# SCH_SrProj_v1_4.net
KiCad netlist of a schematic drawn in EasyEDA
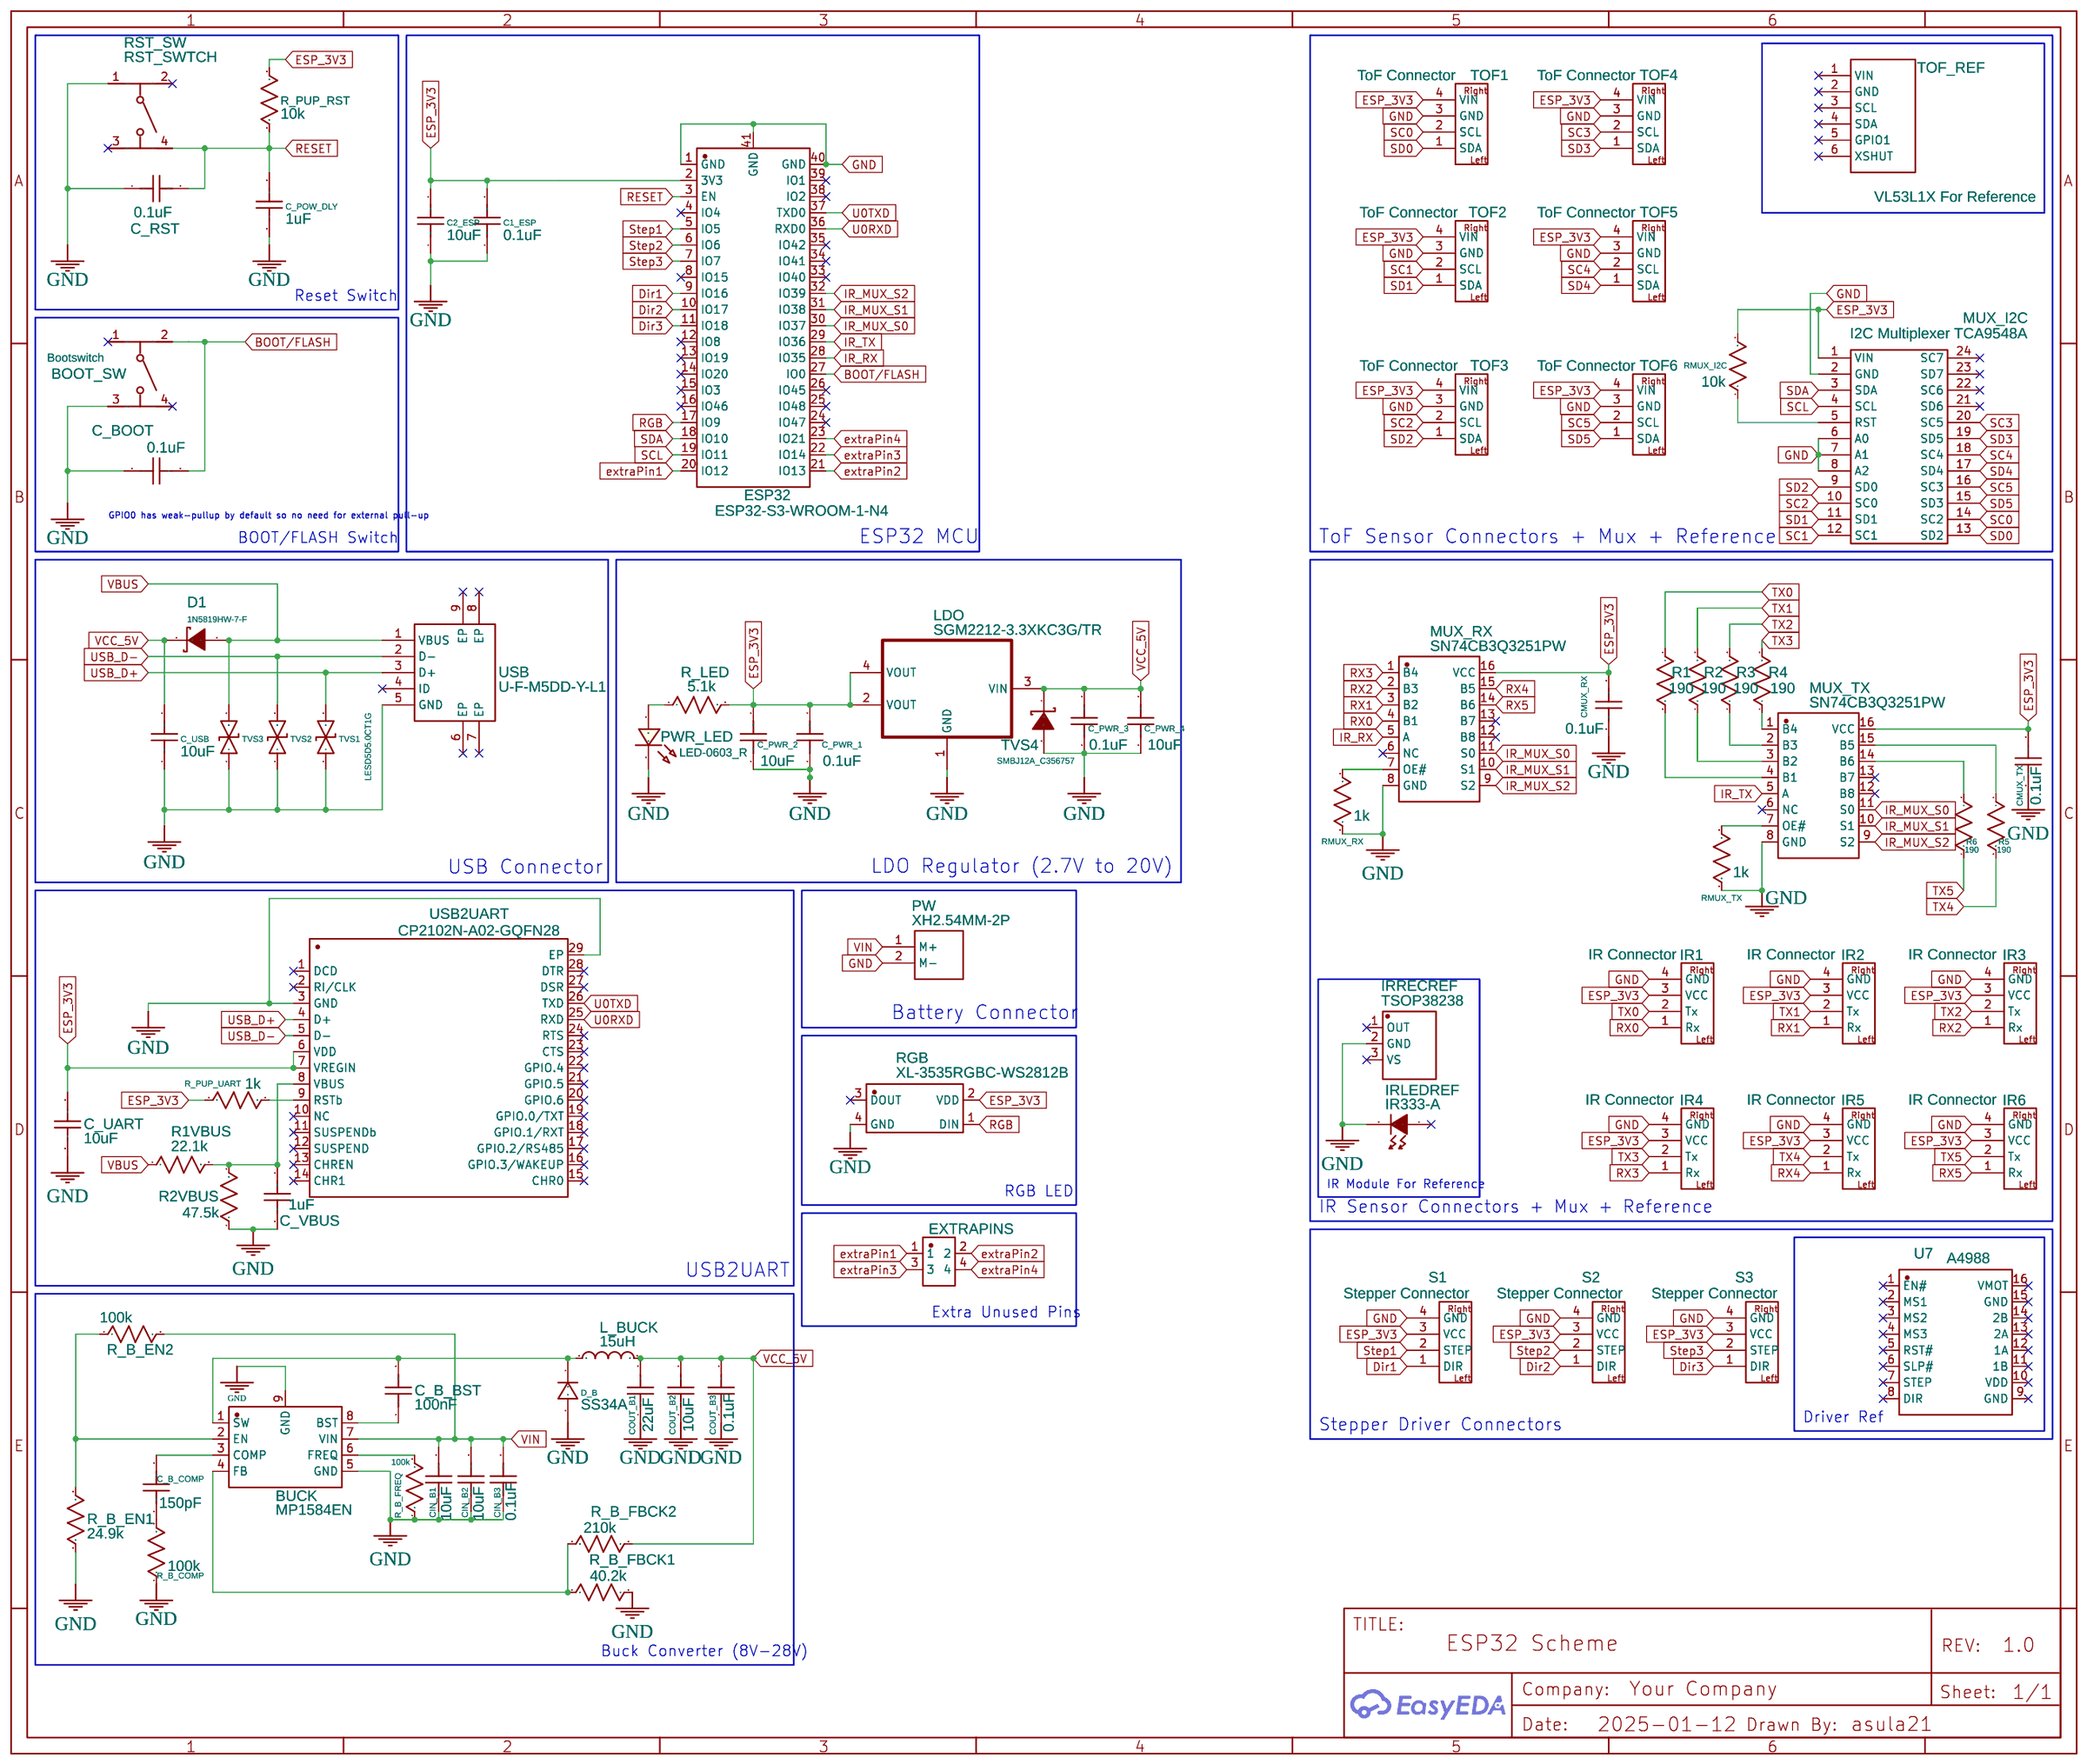
[diagram p0: schematic sheet]

(export (version "E")
  (design (tool "Eeschema 10.0.6"))
  (components
    (comp (ref "BOOT_SW")
      (value "Bootswitch")
      (fields
        (field (name "Manufacturer Part") "Switch,6*6*6Plastic head,260G, 0.25mm,Straight line")
        (field (name "Manufacturer") "BBJ")
      )
      (libsource (lib "") (part "Button-6x6x6mm_1"))
    )
    (comp (ref "BUCK") (value "MP1584EN") (libsource (lib "") (part "MP1584EN")))
    (comp (ref "C1_ESP") (value "0.1uF") (libsource (lib "") (part "C_0603_US_13")))
    (comp (ref "C2_ESP") (value "10uF") (libsource (lib "") (part "C_0603_US_12")))
    (comp (ref "CIN_B1") (value "10uF") (libsource (lib "") (part "C_0603_US_3")))
    (comp (ref "CIN_B2") (value "10uF") (libsource (lib "") (part "C_0603_US_3")))
    (comp (ref "CIN_B3") (value "0.1uF") (libsource (lib "") (part "C_0603_US_3")))
    (comp (ref "CMUX_RX") (value "0.1uF") (libsource (lib "") (part "C_0603_US_10")))
    (comp (ref "CMUX_TX") (value "0.1uF") (libsource (lib "") (part "C_0603_US_5")))
    (comp (ref "COUT_B1") (value "22uF") (libsource (lib "") (part "C_0603_US")))
    (comp (ref "COUT_B2") (value "10uF") (libsource (lib "") (part "C_0603_US")))
    (comp (ref "COUT_B3") (value "0.1uF") (libsource (lib "") (part "C_0603_US")))
    (comp (ref "C_BOOT") (value "0.1uF") (libsource (lib "") (part "C_0603_US_1")))
    (comp (ref "C_B_BST") (value "100nF") (libsource (lib "") (part "C_0603_US_7")))
    (comp (ref "C_B_COMP") (value "150pF") (libsource (lib "") (part "C_0603_US_8")))
    (comp (ref "C_POW_DLY") (value "1uF") (libsource (lib "") (part "C_0603_US_11")))
    (comp (ref "C_PWR_1") (value "0.1uF") (libsource (lib "") (part "C_0603_US_6")))
    (comp (ref "C_PWR_2") (value "10uF") (libsource (lib "") (part "C_0603_US_6")))
    (comp (ref "C_PWR_3") (value "0.1uF") (libsource (lib "") (part "C_0603_US_6")))
    (comp (ref "C_PWR_4") (value "10uF") (libsource (lib "") (part "C_0603_US_6")))
    (comp (ref "C_RST") (value "0.1uF") (libsource (lib "") (part "C_0603_US_9")))
    (comp (ref "C_UART") (value "10uF") (libsource (lib "") (part "C_0603_US_4")))
    (comp (ref "C_USB") (value "10uF") (libsource (lib "") (part "C_0603_US_14")))
    (comp (ref "C_VBUS") (value "1uF") (libsource (lib "") (part "C_0603_US_2")))
    (comp (ref "D1")
      (value "1N5819HW-7-F")
      (fields (field (name "Manufacturer") "DIODES(美台)"))
      (libsource (lib "") (part "1N5819HW-7-F"))
    )
    (comp (ref "D_B")
      (value "SS34A")
      (fields (field (name "Manufacturer") "YANGJIE(扬杰)"))
      (libsource (lib "") (part "SS34A"))
    )
    (comp (ref "ESP32")
      (value "ESP32-S3-WROOM-1-N4")
      (fields (field (name "Manufacturer") "ESPRESSIF(乐鑫)"))
      (libsource (lib "") (part "ESP32-S3-WROOM-1-N4"))
    )
    (comp (ref "EXTRAPINS")
      (value "排母/2.54MM2X2直排母袋装环保")
      (fields
        (field (name "Manufacturer Part") "排母/2.54mm2x2直排母袋装环保")
        (field (name "Manufacturer") "BOOMELE(博穆精密)")
      )
      (libsource (lib "") (part "排母/2.54MM2X2直排母袋装环保"))
    )
    (comp (ref "IR1") (value "IR Connector") (libsource (lib "") (part "MY XH2.54MM.4P_1")))
    (comp (ref "IR2") (value "IR Connector") (libsource (lib "") (part "MY XH2.54MM.4P_1")))
    (comp (ref "IR3") (value "IR Connector") (libsource (lib "") (part "MY XH2.54MM.4P_1")))
    (comp (ref "IR4") (value "IR Connector") (libsource (lib "") (part "MY XH2.54MM.4P_1")))
    (comp (ref "IR5") (value "IR Connector") (libsource (lib "") (part "MY XH2.54MM.4P_1")))
    (comp (ref "IR6") (value "IR Connector") (libsource (lib "") (part "MY XH2.54MM.4P_1")))
    (comp (ref "IRLEDREF")
      (value "IR333-A")
      (fields (field (name "Manufacturer") "EVERLIGHT(亿光)"))
      (libsource (lib "") (part "IR333-A"))
    )
    (comp (ref "IRRECREF")
      (value "TSOP38238")
      (fields (field (name "Manufacturer") "VISHAY(威世)"))
      (libsource (lib "") (part "TSOP38238"))
    )
    (comp (ref "LDO") (value "SGM2212-3.3XKC3G/TR") (libsource (lib "") (part "SGM2212-3.3XKC3G/TR")))
    (comp (ref "L_BUCK")
      (value "15uH")
      (fields (field (name "Manufacturer Part") "CYH127-4.7UH") (field (name "Manufacturer") "SHOU HAN(首韩)"))
      (libsource (lib "") (part "CYH127-4.7UH"))
    )
    (comp (ref "MUX_I2C")
      (value "I2C Multiplexer TCA9548A")
      (fields (field (name "Manufacturer Part") "IDSN-TCA9548A") (field (name "Manufacturer") "IDSN"))
      (libsource (lib "") (part "TCA9548A I2C MULTIPLEXER 8 CHANEL"))
    )
    (comp (ref "MUX_RX")
      (value "SN74CB3Q3251PW")
      (fields (field (name "Manufacturer") "TI(德州仪器)"))
      (libsource (lib "") (part "SN74CB3Q3251PW"))
    )
    (comp (ref "MUX_TX")
      (value "SN74CB3Q3251PW")
      (fields (field (name "Manufacturer") "TI(德州仪器)"))
      (libsource (lib "") (part "SN74CB3Q3251PW_1"))
    )
    (comp (ref "PW")
      (value "XH2.54MM-2P")
      (fields (field (name "Manufacturer Part") "Header P2 PH2.0 TUANLE"))
      (libsource (lib "") (part "PH2.0-2P"))
    )
    (comp (ref "PWR_LED")
      (value "LED-0603_R")
      (fields
        (field (name "Manufacturer Part") "19-217/R6C-AL1M2VY/3T")
        (field (name "Manufacturer") "EVERLIGHT(台湾亿光)")
      )
      (libsource (lib "") (part "LED-0603_R"))
    )
    (comp (ref "R1") (value "190") (libsource (lib "") (part "R_0805_US_1")))
    (comp (ref "R1VBUS") (value "22.1k") (libsource (lib "") (part "R_0603_US_1")))
    (comp (ref "R2") (value "190") (libsource (lib "") (part "R_0805_US")))
    (comp (ref "R2VBUS") (value "47.5k") (libsource (lib "") (part "R_0603_US_3")))
    (comp (ref "R3") (value "190") (libsource (lib "") (part "R_0805_US")))
    (comp (ref "R4") (value "190") (libsource (lib "") (part "R_0805_US")))
    (comp (ref "R5") (value "190") (libsource (lib "") (part "R_0805_US_1")))
    (comp (ref "R6") (value "190") (libsource (lib "") (part "R_0805_US")))
    (comp (ref "RGB")
      (value "XL-3535RGBC-WS2812B")
      (fields (field (name "Manufacturer") "XINGLIGHT(成兴光)"))
      (libsource (lib "") (part "XL-3535RGBC-WS2812B"))
    )
    (comp (ref "RMUX_I2C") (value "10k") (libsource (lib "") (part "R_0603_US_2")))
    (comp (ref "RMUX_RX") (value "1k") (libsource (lib "") (part "R_0603_US_12")))
    (comp (ref "RMUX_TX") (value "1k") (libsource (lib "") (part "R_0603_US_11")))
    (comp (ref "RST_SW")
      (value "RST_SWTCH")
      (fields
        (field (name "Manufacturer Part") "Switch,6*6*6Plastic head,260G, 0.25mm,Straight line")
        (field (name "Manufacturer") "BBJ")
      )
      (libsource (lib "") (part "Button-6x6x6mm"))
    )
    (comp (ref "R_B_COMP") (value "100k") (libsource (lib "") (part "R_0603_US_5")))
    (comp (ref "R_B_EN1") (value "24.9k") (libsource (lib "") (part "R_0603_US_6")))
    (comp (ref "R_B_EN2") (value "100k") (libsource (lib "") (part "R_0603_US")))
    (comp (ref "R_B_FBCK1") (value "40.2k") (libsource (lib "") (part "R_0603_US_13")))
    (comp (ref "R_B_FBCK2") (value "210k") (libsource (lib "") (part "R_0603_US_4")))
    (comp (ref "R_B_FREQ") (value "100k") (libsource (lib "") (part "R_0603_US_9")))
    (comp (ref "R_LED") (value "5.1k") (libsource (lib "") (part "R_0603_US_7")))
    (comp (ref "R_PUP_RST") (value "10k") (libsource (lib "") (part "R_0603_US_8")))
    (comp (ref "R_PUP_UART") (value "1k") (libsource (lib "") (part "R_0603_US_10")))
    (comp (ref "S1") (value "Stepper Connector") (libsource (lib "") (part "MY XH2.54MM.4P_2")))
    (comp (ref "S2") (value "Stepper Connector") (libsource (lib "") (part "MY XH2.54MM.4P_2")))
    (comp (ref "S3") (value "Stepper Connector") (libsource (lib "") (part "MY XH2.54MM.4P_2")))
    (comp (ref "TOF1") (value "ToF Connector") (libsource (lib "") (part "MY XH2.54MM.4P")))
    (comp (ref "TOF2") (value "ToF Connector") (libsource (lib "") (part "MY XH2.54MM.4P")))
    (comp (ref "TOF3") (value "ToF Connector") (libsource (lib "") (part "MY XH2.54MM.4P")))
    (comp (ref "TOF4") (value "ToF Connector") (libsource (lib "") (part "MY XH2.54MM.4P")))
    (comp (ref "TOF5") (value "ToF Connector") (libsource (lib "") (part "MY XH2.54MM.4P")))
    (comp (ref "TOF6") (value "ToF Connector") (libsource (lib "") (part "MY XH2.54MM.4P")))
    (comp (ref "TOF_REF")
      (value "VL53L1X For Reference")
      (fields (field (name "Manufacturer Part") "VL53L0X Time-of-Flight Distance Sensor VL53L0X"))
      (libsource (lib "") (part "VL53L1X_BREAKOUT"))
    )
    (comp (ref "TVS1")
      (value "LESD5D5.0CT1G")
      (fields (field (name "Manufacturer") "LRC(乐山无线电)"))
      (libsource (lib "") (part "LESD5D5.0CT1G"))
    )
    (comp (ref "TVS2")
      (value "LESD5D5.0CT1G")
      (fields (field (name "Manufacturer") "LRC(乐山无线电)"))
      (libsource (lib "") (part "LESD5D5.0CT1G"))
    )
    (comp (ref "TVS3")
      (value "LESD5D5.0CT1G")
      (fields (field (name "Manufacturer") "LRC(乐山无线电)"))
      (libsource (lib "") (part "LESD5D5.0CT1G"))
    )
    (comp (ref "TVS4")
      (value "SMBJ12A_C356757")
      (fields (field (name "Manufacturer Part") "SMBJ12A") (field (name "Manufacturer") "JJW(捷捷微)"))
      (libsource (lib "") (part "SMBJ12A_C356757"))
    )
    (comp (ref "U7") (value "A4988") (libsource (lib "") (part "A4988")))
    (comp (ref "USB")
      (value "U-F-M5DD-Y-L1")
      (fields (field (name "Manufacturer") "韩国韩荣"))
      (libsource (lib "") (part "U-F-M5DD-Y-L1"))
    )
    (comp (ref "USB2UART")
      (value "CP2102N-A02-GQFN28")
      (fields (field (name "Manufacturer") "SKYWORKS/SILICON LABS(芯科)"))
      (libsource (lib "") (part "CP2102N-A02-GQFN28"))
    )
  )
  (nets
    (net (code "1") (name "BOOT{slash}FLASH") (class "Default")
      (node (ref "BOOT_SW") (pin "2") (pinfunction "2_2") (pintype "unspecified"))
      (node (ref "C_BOOT") (pin "2") (pinfunction "2_2") (pintype "unspecified"))
      (node (ref "ESP32") (pin "27") (pinfunction "IO0_27") (pintype "unspecified"))
    )
    (net (code "2") (name "Dir1") (class "Default")
      (node (ref "ESP32") (pin "9") (pinfunction "IO16_9") (pintype "unspecified"))
      (node (ref "S1") (pin "1") (pinfunction "DIR_1") (pintype "unspecified"))
    )
    (net (code "3") (name "Dir2") (class "Default")
      (node (ref "ESP32") (pin "10") (pinfunction "IO17_10") (pintype "unspecified"))
      (node (ref "S2") (pin "1") (pinfunction "DIR_1") (pintype "unspecified"))
    )
    (net (code "4") (name "Dir3") (class "Default")
      (node (ref "ESP32") (pin "11") (pinfunction "IO18_11") (pintype "unspecified"))
      (node (ref "S3") (pin "1") (pinfunction "DIR_1") (pintype "unspecified"))
    )
    (net (code "5") (name "ESP_3V3") (class "Default")
      (node (ref "C1_ESP") (pin "2") (pinfunction "2_2") (pintype "unspecified"))
      (node (ref "C2_ESP") (pin "2") (pinfunction "2_2") (pintype "unspecified"))
      (node (ref "CMUX_RX") (pin "2") (pinfunction "2_2") (pintype "unspecified"))
      (node (ref "CMUX_TX") (pin "2") (pinfunction "2_2") (pintype "unspecified"))
      (node (ref "C_PWR_1") (pin "2") (pinfunction "2_2") (pintype "unspecified"))
      (node (ref "C_PWR_2") (pin "2") (pinfunction "2_2") (pintype "unspecified"))
      (node (ref "C_UART") (pin "2") (pinfunction "2_2") (pintype "unspecified"))
      (node (ref "ESP32") (pin "2") (pinfunction "3V3_2") (pintype "unspecified"))
      (node (ref "IR1") (pin "3") (pinfunction "VCC_3") (pintype "unspecified"))
      (node (ref "IR2") (pin "3") (pinfunction "VCC_3") (pintype "unspecified"))
      (node (ref "IR3") (pin "3") (pinfunction "VCC_3") (pintype "unspecified"))
      (node (ref "IR4") (pin "3") (pinfunction "VCC_3") (pintype "unspecified"))
      (node (ref "IR5") (pin "3") (pinfunction "VCC_3") (pintype "unspecified"))
      (node (ref "IR6") (pin "3") (pinfunction "VCC_3") (pintype "unspecified"))
      (node (ref "LDO") (pin "2") (pinfunction "VOUT_2") (pintype "unspecified"))
      (node (ref "LDO") (pin "4") (pinfunction "VOUT_4") (pintype "unspecified"))
      (node (ref "MUX_I2C") (pin "1") (pinfunction "VIN_1") (pintype "unspecified"))
      (node (ref "MUX_RX") (pin "16") (pinfunction "VCC_16") (pintype "unspecified"))
      (node (ref "MUX_TX") (pin "16") (pinfunction "VCC_16") (pintype "unspecified"))
      (node (ref "RGB") (pin "2") (pinfunction "VDD_2") (pintype "unspecified"))
      (node (ref "RMUX_I2C") (pin "2") (pinfunction "2_2") (pintype "unspecified"))
      (node (ref "R_LED") (pin "2") (pinfunction "2_2") (pintype "unspecified"))
      (node (ref "R_PUP_RST") (pin "2") (pinfunction "2_2") (pintype "unspecified"))
      (node (ref "R_PUP_UART") (pin "2") (pinfunction "2_2") (pintype "unspecified"))
      (node (ref "S1") (pin "3") (pinfunction "VCC_3") (pintype "unspecified"))
      (node (ref "S2") (pin "3") (pinfunction "VCC_3") (pintype "unspecified"))
      (node (ref "S3") (pin "3") (pinfunction "VCC_3") (pintype "unspecified"))
      (node (ref "TOF1") (pin "4") (pinfunction "VIN_4") (pintype "unspecified"))
      (node (ref "TOF2") (pin "4") (pinfunction "VIN_4") (pintype "unspecified"))
      (node (ref "TOF3") (pin "4") (pinfunction "VIN_4") (pintype "unspecified"))
      (node (ref "TOF4") (pin "4") (pinfunction "VIN_4") (pintype "unspecified"))
      (node (ref "TOF5") (pin "4") (pinfunction "VIN_4") (pintype "unspecified"))
      (node (ref "TOF6") (pin "4") (pinfunction "VIN_4") (pintype "unspecified"))
      (node (ref "USB2UART") (pin "6") (pinfunction "VDD_6") (pintype "unspecified"))
      (node (ref "USB2UART") (pin "7") (pinfunction "VREGIN_7") (pintype "unspecified"))
    )
    (net (code "6") (name "GND") (class "Default")
      (node (ref "BOOT_SW") (pin "3") (pinfunction "3_3") (pintype "unspecified"))
      (node (ref "BUCK") (pin "5") (pinfunction "GND_5") (pintype "unspecified"))
      (node (ref "BUCK") (pin "9") (pinfunction "GND_9") (pintype "unspecified"))
      (node (ref "C1_ESP") (pin "1") (pinfunction "1_1") (pintype "unspecified"))
      (node (ref "C2_ESP") (pin "1") (pinfunction "1_1") (pintype "unspecified"))
      (node (ref "CIN_B1") (pin "1") (pinfunction "1_1") (pintype "unspecified"))
      (node (ref "CIN_B2") (pin "1") (pinfunction "1_1") (pintype "unspecified"))
      (node (ref "CIN_B3") (pin "1") (pinfunction "1_1") (pintype "unspecified"))
      (node (ref "CMUX_RX") (pin "1") (pinfunction "1_1") (pintype "unspecified"))
      (node (ref "CMUX_TX") (pin "1") (pinfunction "1_1") (pintype "unspecified"))
      (node (ref "COUT_B1") (pin "1") (pinfunction "1_1") (pintype "unspecified"))
      (node (ref "COUT_B2") (pin "1") (pinfunction "1_1") (pintype "unspecified"))
      (node (ref "COUT_B3") (pin "1") (pinfunction "1_1") (pintype "unspecified"))
      (node (ref "C_BOOT") (pin "1") (pinfunction "1_1") (pintype "unspecified"))
      (node (ref "C_POW_DLY") (pin "1") (pinfunction "1_1") (pintype "unspecified"))
      (node (ref "C_PWR_1") (pin "1") (pinfunction "1_1") (pintype "unspecified"))
      (node (ref "C_PWR_2") (pin "1") (pinfunction "1_1") (pintype "unspecified"))
      (node (ref "C_PWR_3") (pin "1") (pinfunction "1_1") (pintype "unspecified"))
      (node (ref "C_PWR_4") (pin "1") (pinfunction "1_1") (pintype "unspecified"))
      (node (ref "C_RST") (pin "1") (pinfunction "1_1") (pintype "unspecified"))
      (node (ref "C_UART") (pin "1") (pinfunction "1_1") (pintype "unspecified"))
      (node (ref "C_USB") (pin "1") (pinfunction "1_1") (pintype "unspecified"))
      (node (ref "C_VBUS") (pin "2") (pinfunction "2_2") (pintype "unspecified"))
      (node (ref "D_B") (pin "2") (pinfunction "A_2") (pintype "unspecified"))
      (node (ref "ESP32") (pin "1") (pinfunction "GND_1") (pintype "unspecified"))
      (node (ref "ESP32") (pin "40") (pinfunction "GND_40") (pintype "unspecified"))
      (node (ref "ESP32") (pin "41") (pinfunction "GND_41") (pintype "unspecified"))
      (node (ref "IR1") (pin "4") (pinfunction "GND_4") (pintype "unspecified"))
      (node (ref "IR2") (pin "4") (pinfunction "GND_4") (pintype "unspecified"))
      (node (ref "IR3") (pin "4") (pinfunction "GND_4") (pintype "unspecified"))
      (node (ref "IR4") (pin "4") (pinfunction "GND_4") (pintype "unspecified"))
      (node (ref "IR5") (pin "4") (pinfunction "GND_4") (pintype "unspecified"))
      (node (ref "IR6") (pin "4") (pinfunction "GND_4") (pintype "unspecified"))
      (node (ref "IRLEDREF") (pin "2") (pinfunction "C_2") (pintype "input"))
      (node (ref "IRRECREF") (pin "2") (pinfunction "GND_2") (pintype "unspecified"))
      (node (ref "LDO") (pin "1") (pinfunction "GND_1") (pintype "unspecified"))
      (node (ref "MUX_I2C") (pin "2") (pinfunction "GND_2") (pintype "unspecified"))
      (node (ref "MUX_I2C") (pin "6") (pinfunction "A0_6") (pintype "unspecified"))
      (node (ref "MUX_I2C") (pin "7") (pinfunction "A1_7") (pintype "unspecified"))
      (node (ref "MUX_I2C") (pin "8") (pinfunction "A2_8") (pintype "unspecified"))
      (node (ref "MUX_RX") (pin "8") (pinfunction "GND_8") (pintype "unspecified"))
      (node (ref "MUX_TX") (pin "8") (pinfunction "GND_8") (pintype "unspecified"))
      (node (ref "PW") (pin "2") (pinfunction "M-_2") (pintype "unspecified"))
      (node (ref "PWR_LED") (pin "2") (pinfunction "2_2") (pintype "unspecified"))
      (node (ref "R2VBUS") (pin "1") (pinfunction "1_1") (pintype "unspecified"))
      (node (ref "RGB") (pin "4") (pinfunction "GND_4") (pintype "unspecified"))
      (node (ref "RMUX_RX") (pin "1") (pinfunction "1_1") (pintype "unspecified"))
      (node (ref "RMUX_TX") (pin "1") (pinfunction "1_1") (pintype "unspecified"))
      (node (ref "RST_SW") (pin "1") (pinfunction "1_1") (pintype "unspecified"))
      (node (ref "R_B_COMP") (pin "1") (pinfunction "1_1") (pintype "unspecified"))
      (node (ref "R_B_EN1") (pin "1") (pinfunction "1_1") (pintype "unspecified"))
      (node (ref "R_B_FBCK1") (pin "2") (pinfunction "2_2") (pintype "unspecified"))
      (node (ref "R_B_FREQ") (pin "1") (pinfunction "1_1") (pintype "unspecified"))
      (node (ref "S1") (pin "4") (pinfunction "GND_4") (pintype "unspecified"))
      (node (ref "S2") (pin "4") (pinfunction "GND_4") (pintype "unspecified"))
      (node (ref "S3") (pin "4") (pinfunction "GND_4") (pintype "unspecified"))
      (node (ref "TOF1") (pin "3") (pinfunction "GND_3") (pintype "unspecified"))
      (node (ref "TOF2") (pin "3") (pinfunction "GND_3") (pintype "unspecified"))
      (node (ref "TOF3") (pin "3") (pinfunction "GND_3") (pintype "unspecified"))
      (node (ref "TOF4") (pin "3") (pinfunction "GND_3") (pintype "unspecified"))
      (node (ref "TOF5") (pin "3") (pinfunction "GND_3") (pintype "unspecified"))
      (node (ref "TOF6") (pin "3") (pinfunction "GND_3") (pintype "unspecified"))
      (node (ref "TVS1") (pin "1") (pinfunction "1_1") (pintype "unspecified"))
      (node (ref "TVS2") (pin "1") (pinfunction "1_1") (pintype "unspecified"))
      (node (ref "TVS3") (pin "1") (pinfunction "1_1") (pintype "unspecified"))
      (node (ref "TVS4") (pin "2") (pinfunction "A_2") (pintype "unspecified"))
      (node (ref "USB") (pin "5") (pinfunction "GND_5") (pintype "unspecified"))
      (node (ref "USB2UART") (pin "29") (pinfunction "EP_29") (pintype "unspecified"))
      (node (ref "USB2UART") (pin "3") (pinfunction "GND_3") (pintype "unspecified"))
    )
    (net (code "7") (name "IR_MUX_S0") (class "Default")
      (node (ref "ESP32") (pin "30") (pinfunction "IO37_30") (pintype "unspecified"))
      (node (ref "MUX_RX") (pin "11") (pinfunction "S0_11") (pintype "unspecified"))
      (node (ref "MUX_TX") (pin "11") (pinfunction "S0_11") (pintype "unspecified"))
    )
    (net (code "8") (name "IR_MUX_S1") (class "Default")
      (node (ref "ESP32") (pin "31") (pinfunction "IO38_31") (pintype "unspecified"))
      (node (ref "MUX_RX") (pin "10") (pinfunction "S1_10") (pintype "unspecified"))
      (node (ref "MUX_TX") (pin "10") (pinfunction "S1_10") (pintype "unspecified"))
    )
    (net (code "9") (name "IR_MUX_S2") (class "Default")
      (node (ref "ESP32") (pin "32") (pinfunction "IO39_32") (pintype "unspecified"))
      (node (ref "MUX_RX") (pin "9") (pinfunction "S2_9") (pintype "unspecified"))
      (node (ref "MUX_TX") (pin "9") (pinfunction "S2_9") (pintype "unspecified"))
    )
    (net (code "10") (name "IR_RX") (class "Default")
      (node (ref "ESP32") (pin "28") (pinfunction "IO35_28") (pintype "unspecified"))
      (node (ref "MUX_RX") (pin "5") (pinfunction "A_5") (pintype "unspecified"))
    )
    (net (code "11") (name "IR_TX") (class "Default")
      (node (ref "ESP32") (pin "29") (pinfunction "IO36_29") (pintype "unspecified"))
      (node (ref "MUX_TX") (pin "5") (pinfunction "A_5") (pintype "unspecified"))
    )
    (net (code "12") (name "Net-(BUCK-BST)") (class "Default")
      (node (ref "BUCK") (pin "8") (pinfunction "BST_8") (pintype "unspecified"))
      (node (ref "C_B_BST") (pin "1") (pinfunction "1_1") (pintype "unspecified"))
    )
    (net (code "13") (name "Net-(BUCK-COMP)") (class "Default")
      (node (ref "BUCK") (pin "3") (pinfunction "COMP_3") (pintype "unspecified"))
      (node (ref "C_B_COMP") (pin "2") (pinfunction "2_2") (pintype "unspecified"))
    )
    (net (code "14") (name "Net-(BUCK-EN)") (class "Default")
      (node (ref "BUCK") (pin "2") (pinfunction "EN_2") (pintype "unspecified"))
      (node (ref "R_B_EN1") (pin "2") (pinfunction "2_2") (pintype "unspecified"))
      (node (ref "R_B_EN2") (pin "1") (pinfunction "1_1") (pintype "unspecified"))
    )
    (net (code "15") (name "Net-(BUCK-FB)") (class "Default")
      (node (ref "BUCK") (pin "4") (pinfunction "FB_4") (pintype "unspecified"))
      (node (ref "R_B_FBCK1") (pin "1") (pinfunction "1_1") (pintype "unspecified"))
      (node (ref "R_B_FBCK2") (pin "2") (pinfunction "2_2") (pintype "unspecified"))
    )
    (net (code "16") (name "Net-(BUCK-FREQ)") (class "Default")
      (node (ref "BUCK") (pin "6") (pinfunction "FREQ_6") (pintype "unspecified"))
      (node (ref "R_B_FREQ") (pin "2") (pinfunction "2_2") (pintype "unspecified"))
    )
    (net (code "17") (name "Net-(BUCK-SW)") (class "Default")
      (node (ref "BUCK") (pin "1") (pinfunction "SW_1") (pintype "unspecified"))
      (node (ref "C_B_BST") (pin "2") (pinfunction "2_2") (pintype "unspecified"))
      (node (ref "D_B") (pin "1") (pinfunction "C_1") (pintype "unspecified"))
      (node (ref "L_BUCK") (pin "1") (pinfunction "1_1") (pintype "unspecified"))
    )
    (net (code "18") (name "Net-(C_B_COMP-Pad1)") (class "Default")
      (node (ref "C_B_COMP") (pin "1") (pinfunction "1_1") (pintype "unspecified"))
      (node (ref "R_B_COMP") (pin "2") (pinfunction "2_2") (pintype "unspecified"))
    )
    (net (code "19") (name "Net-(MUX_I2C-RST)") (class "Default")
      (node (ref "MUX_I2C") (pin "5") (pinfunction "RST_5") (pintype "unspecified"))
      (node (ref "RMUX_I2C") (pin "1") (pinfunction "1_1") (pintype "unspecified"))
    )
    (net (code "20") (name "Net-(MUX_RX-OE#)") (class "Default")
      (node (ref "MUX_RX") (pin "7") (pinfunction "OE#_7") (pintype "unspecified"))
      (node (ref "RMUX_RX") (pin "2") (pinfunction "2_2") (pintype "unspecified"))
    )
    (net (code "21") (name "Net-(MUX_TX-B1)") (class "Default")
      (node (ref "MUX_TX") (pin "4") (pinfunction "B1_4") (pintype "unspecified"))
      (node (ref "R1") (pin "2") (pinfunction "2_2") (pintype "unspecified"))
    )
    (net (code "22") (name "Net-(MUX_TX-B2)") (class "Default")
      (node (ref "MUX_TX") (pin "3") (pinfunction "B2_3") (pintype "unspecified"))
      (node (ref "R2") (pin "1") (pinfunction "1_1") (pintype "unspecified"))
    )
    (net (code "23") (name "Net-(MUX_TX-B3)") (class "Default")
      (node (ref "MUX_TX") (pin "2") (pinfunction "B3_2") (pintype "unspecified"))
      (node (ref "R3") (pin "1") (pinfunction "1_1") (pintype "unspecified"))
    )
    (net (code "24") (name "Net-(MUX_TX-B4)") (class "Default")
      (node (ref "MUX_TX") (pin "1") (pinfunction "B4_1") (pintype "unspecified"))
      (node (ref "R4") (pin "1") (pinfunction "1_1") (pintype "unspecified"))
    )
    (net (code "25") (name "Net-(MUX_TX-B5)") (class "Default")
      (node (ref "MUX_TX") (pin "15") (pinfunction "B5_15") (pintype "unspecified"))
      (node (ref "R5") (pin "1") (pinfunction "1_1") (pintype "unspecified"))
    )
    (net (code "26") (name "Net-(MUX_TX-B6)") (class "Default")
      (node (ref "MUX_TX") (pin "14") (pinfunction "B6_14") (pintype "unspecified"))
      (node (ref "R6") (pin "2") (pinfunction "2_2") (pintype "unspecified"))
    )
    (net (code "27") (name "Net-(MUX_TX-OE#)") (class "Default")
      (node (ref "MUX_TX") (pin "7") (pinfunction "OE#_7") (pintype "unspecified"))
      (node (ref "RMUX_TX") (pin "2") (pinfunction "2_2") (pintype "unspecified"))
    )
    (net (code "28") (name "Net-(PWR_LED-Pad1)") (class "Default")
      (node (ref "PWR_LED") (pin "1") (pinfunction "1_1") (pintype "unspecified"))
      (node (ref "R_LED") (pin "1") (pinfunction "1_1") (pintype "unspecified"))
    )
    (net (code "29") (name "Net-(USB2UART-RSTb)") (class "Default")
      (node (ref "R_PUP_UART") (pin "1") (pinfunction "1_1") (pintype "unspecified"))
      (node (ref "USB2UART") (pin "9") (pinfunction "RSTb_9") (pintype "unspecified"))
    )
    (net (code "30") (name "Net-(USB2UART-VBUS)") (class "Default")
      (node (ref "C_VBUS") (pin "1") (pinfunction "1_1") (pintype "unspecified"))
      (node (ref "R1VBUS") (pin "2") (pinfunction "2_2") (pintype "unspecified"))
      (node (ref "R2VBUS") (pin "2") (pinfunction "2_2") (pintype "unspecified"))
      (node (ref "USB2UART") (pin "8") (pinfunction "VBUS_8") (pintype "unspecified"))
    )
    (net (code "31") (name "RESET") (class "Default")
      (node (ref "C_POW_DLY") (pin "2") (pinfunction "2_2") (pintype "unspecified"))
      (node (ref "C_RST") (pin "2") (pinfunction "2_2") (pintype "unspecified"))
      (node (ref "ESP32") (pin "3") (pinfunction "EN_3") (pintype "unspecified"))
      (node (ref "RST_SW") (pin "4") (pinfunction "4_4") (pintype "unspecified"))
      (node (ref "R_PUP_RST") (pin "1") (pinfunction "1_1") (pintype "unspecified"))
    )
    (net (code "32") (name "RGB") (class "Default")
      (node (ref "ESP32") (pin "17") (pinfunction "IO9_17") (pintype "unspecified"))
      (node (ref "RGB") (pin "1") (pinfunction "DIN_1") (pintype "unspecified"))
    )
    (net (code "33") (name "RX0") (class "Default")
      (node (ref "IR1") (pin "1") (pinfunction "Rx_1") (pintype "unspecified"))
      (node (ref "MUX_RX") (pin "4") (pinfunction "B1_4") (pintype "unspecified"))
    )
    (net (code "34") (name "RX1") (class "Default")
      (node (ref "IR2") (pin "1") (pinfunction "Rx_1") (pintype "unspecified"))
      (node (ref "MUX_RX") (pin "3") (pinfunction "B2_3") (pintype "unspecified"))
    )
    (net (code "35") (name "RX2") (class "Default")
      (node (ref "IR3") (pin "1") (pinfunction "Rx_1") (pintype "unspecified"))
      (node (ref "MUX_RX") (pin "2") (pinfunction "B3_2") (pintype "unspecified"))
    )
    (net (code "36") (name "RX3") (class "Default")
      (node (ref "IR4") (pin "1") (pinfunction "Rx_1") (pintype "unspecified"))
      (node (ref "MUX_RX") (pin "1") (pinfunction "B4_1") (pintype "unspecified"))
    )
    (net (code "37") (name "RX4") (class "Default")
      (node (ref "IR5") (pin "1") (pinfunction "Rx_1") (pintype "unspecified"))
      (node (ref "MUX_RX") (pin "15") (pinfunction "B5_15") (pintype "unspecified"))
    )
    (net (code "38") (name "RX5") (class "Default")
      (node (ref "IR6") (pin "1") (pinfunction "Rx_1") (pintype "unspecified"))
      (node (ref "MUX_RX") (pin "14") (pinfunction "B6_14") (pintype "unspecified"))
    )
    (net (code "39") (name "SC0") (class "Default")
      (node (ref "MUX_I2C") (pin "14") (pinfunction "SC2_14") (pintype "unspecified"))
      (node (ref "TOF1") (pin "2") (pinfunction "SCL_2") (pintype "unspecified"))
    )
    (net (code "40") (name "SC1") (class "Default")
      (node (ref "MUX_I2C") (pin "12") (pinfunction "SC1_12") (pintype "unspecified"))
      (node (ref "TOF2") (pin "2") (pinfunction "SCL_2") (pintype "unspecified"))
    )
    (net (code "41") (name "SC2") (class "Default")
      (node (ref "MUX_I2C") (pin "10") (pinfunction "SC0_10") (pintype "unspecified"))
      (node (ref "TOF3") (pin "2") (pinfunction "SCL_2") (pintype "unspecified"))
    )
    (net (code "42") (name "SC3") (class "Default")
      (node (ref "MUX_I2C") (pin "20") (pinfunction "SC5_20") (pintype "unspecified"))
      (node (ref "TOF4") (pin "2") (pinfunction "SCL_2") (pintype "unspecified"))
    )
    (net (code "43") (name "SC4") (class "Default")
      (node (ref "MUX_I2C") (pin "18") (pinfunction "SC4_18") (pintype "unspecified"))
      (node (ref "TOF5") (pin "2") (pinfunction "SCL_2") (pintype "unspecified"))
    )
    (net (code "44") (name "SC5") (class "Default")
      (node (ref "MUX_I2C") (pin "16") (pinfunction "SC3_16") (pintype "unspecified"))
      (node (ref "TOF6") (pin "2") (pinfunction "SCL_2") (pintype "unspecified"))
    )
    (net (code "45") (name "SCL") (class "Default")
      (node (ref "ESP32") (pin "19") (pinfunction "IO11_19") (pintype "unspecified"))
      (node (ref "MUX_I2C") (pin "4") (pinfunction "SCL_4") (pintype "unspecified"))
    )
    (net (code "46") (name "SD0") (class "Default")
      (node (ref "MUX_I2C") (pin "13") (pinfunction "SD2_13") (pintype "unspecified"))
      (node (ref "TOF1") (pin "1") (pinfunction "SDA_1") (pintype "unspecified"))
    )
    (net (code "47") (name "SD1") (class "Default")
      (node (ref "MUX_I2C") (pin "11") (pinfunction "SD1_11") (pintype "unspecified"))
      (node (ref "TOF2") (pin "1") (pinfunction "SDA_1") (pintype "unspecified"))
    )
    (net (code "48") (name "SD2") (class "Default")
      (node (ref "MUX_I2C") (pin "9") (pinfunction "SD0_9") (pintype "unspecified"))
      (node (ref "TOF3") (pin "1") (pinfunction "SDA_1") (pintype "unspecified"))
    )
    (net (code "49") (name "SD3") (class "Default")
      (node (ref "MUX_I2C") (pin "19") (pinfunction "SD5_19") (pintype "unspecified"))
      (node (ref "TOF4") (pin "1") (pinfunction "SDA_1") (pintype "unspecified"))
    )
    (net (code "50") (name "SD4") (class "Default")
      (node (ref "MUX_I2C") (pin "17") (pinfunction "SD4_17") (pintype "unspecified"))
      (node (ref "TOF5") (pin "1") (pinfunction "SDA_1") (pintype "unspecified"))
    )
    (net (code "51") (name "SD5") (class "Default")
      (node (ref "MUX_I2C") (pin "15") (pinfunction "SD3_15") (pintype "unspecified"))
      (node (ref "TOF6") (pin "1") (pinfunction "SDA_1") (pintype "unspecified"))
    )
    (net (code "52") (name "SDA") (class "Default")
      (node (ref "ESP32") (pin "18") (pinfunction "IO10_18") (pintype "unspecified"))
      (node (ref "MUX_I2C") (pin "3") (pinfunction "SDA_3") (pintype "unspecified"))
    )
    (net (code "53") (name "Step1") (class "Default")
      (node (ref "ESP32") (pin "5") (pinfunction "IO5_5") (pintype "unspecified"))
      (node (ref "S1") (pin "2") (pinfunction "STEP_2") (pintype "unspecified"))
    )
    (net (code "54") (name "Step2") (class "Default")
      (node (ref "ESP32") (pin "6") (pinfunction "IO6_6") (pintype "unspecified"))
      (node (ref "S2") (pin "2") (pinfunction "STEP_2") (pintype "unspecified"))
    )
    (net (code "55") (name "Step3") (class "Default")
      (node (ref "ESP32") (pin "7") (pinfunction "IO7_7") (pintype "unspecified"))
      (node (ref "S3") (pin "2") (pinfunction "STEP_2") (pintype "unspecified"))
    )
    (net (code "56") (name "TX0") (class "Default")
      (node (ref "IR1") (pin "2") (pinfunction "Tx_2") (pintype "unspecified"))
      (node (ref "R1") (pin "1") (pinfunction "1_1") (pintype "unspecified"))
    )
    (net (code "57") (name "TX1") (class "Default")
      (node (ref "IR2") (pin "2") (pinfunction "Tx_2") (pintype "unspecified"))
      (node (ref "R2") (pin "2") (pinfunction "2_2") (pintype "unspecified"))
    )
    (net (code "58") (name "TX2") (class "Default")
      (node (ref "IR3") (pin "2") (pinfunction "Tx_2") (pintype "unspecified"))
      (node (ref "R3") (pin "2") (pinfunction "2_2") (pintype "unspecified"))
    )
    (net (code "59") (name "TX3") (class "Default")
      (node (ref "IR4") (pin "2") (pinfunction "Tx_2") (pintype "unspecified"))
      (node (ref "R4") (pin "2") (pinfunction "2_2") (pintype "unspecified"))
    )
    (net (code "60") (name "TX4") (class "Default")
      (node (ref "IR5") (pin "2") (pinfunction "Tx_2") (pintype "unspecified"))
      (node (ref "R5") (pin "2") (pinfunction "2_2") (pintype "unspecified"))
    )
    (net (code "61") (name "TX5") (class "Default")
      (node (ref "IR6") (pin "2") (pinfunction "Tx_2") (pintype "unspecified"))
      (node (ref "R6") (pin "1") (pinfunction "1_1") (pintype "unspecified"))
    )
    (net (code "62") (name "U0RXD") (class "Default")
      (node (ref "ESP32") (pin "36") (pinfunction "RXD0_36") (pintype "unspecified"))
      (node (ref "USB2UART") (pin "25") (pinfunction "RXD_25") (pintype "unspecified"))
    )
    (net (code "63") (name "U0TXD") (class "Default")
      (node (ref "ESP32") (pin "37") (pinfunction "TXD0_37") (pintype "unspecified"))
      (node (ref "USB2UART") (pin "26") (pinfunction "TXD_26") (pintype "unspecified"))
    )
    (net (code "64") (name "USB_D+") (class "Default")
      (node (ref "TVS1") (pin "2") (pinfunction "2_2") (pintype "unspecified"))
      (node (ref "USB") (pin "3") (pinfunction "D+_3") (pintype "unspecified"))
      (node (ref "USB2UART") (pin "4") (pinfunction "D+_4") (pintype "unspecified"))
    )
    (net (code "65") (name "USB_D-") (class "Default")
      (node (ref "TVS2") (pin "2") (pinfunction "2_2") (pintype "unspecified"))
      (node (ref "USB") (pin "2") (pinfunction "D-_2") (pintype "unspecified"))
      (node (ref "USB2UART") (pin "5") (pinfunction "D-_5") (pintype "unspecified"))
    )
    (net (code "66") (name "VBUS") (class "Default")
      (node (ref "D1") (pin "2") (pinfunction "A_2") (pintype "unspecified"))
      (node (ref "R1VBUS") (pin "1") (pinfunction "1_1") (pintype "unspecified"))
      (node (ref "TVS3") (pin "2") (pinfunction "2_2") (pintype "unspecified"))
      (node (ref "USB") (pin "1") (pinfunction "VBUS_1") (pintype "unspecified"))
    )
    (net (code "67") (name "VCC_5V") (class "Default")
      (node (ref "COUT_B1") (pin "2") (pinfunction "2_2") (pintype "unspecified"))
      (node (ref "COUT_B2") (pin "2") (pinfunction "2_2") (pintype "unspecified"))
      (node (ref "COUT_B3") (pin "2") (pinfunction "2_2") (pintype "unspecified"))
      (node (ref "C_PWR_3") (pin "2") (pinfunction "2_2") (pintype "unspecified"))
      (node (ref "C_PWR_4") (pin "2") (pinfunction "2_2") (pintype "unspecified"))
      (node (ref "C_USB") (pin "2") (pinfunction "2_2") (pintype "unspecified"))
      (node (ref "D1") (pin "1") (pinfunction "K_1") (pintype "unspecified"))
      (node (ref "LDO") (pin "3") (pinfunction "VIN_3") (pintype "unspecified"))
      (node (ref "L_BUCK") (pin "2") (pinfunction "2_2") (pintype "unspecified"))
      (node (ref "R_B_FBCK2") (pin "1") (pinfunction "1_1") (pintype "unspecified"))
      (node (ref "TVS4") (pin "1") (pinfunction "K_1") (pintype "unspecified"))
    )
    (net (code "68") (name "VIN") (class "Default")
      (node (ref "BUCK") (pin "7") (pinfunction "VIN_7") (pintype "unspecified"))
      (node (ref "CIN_B1") (pin "2") (pinfunction "2_2") (pintype "unspecified"))
      (node (ref "CIN_B2") (pin "2") (pinfunction "2_2") (pintype "unspecified"))
      (node (ref "CIN_B3") (pin "2") (pinfunction "2_2") (pintype "unspecified"))
      (node (ref "PW") (pin "1") (pinfunction "M+_1") (pintype "unspecified"))
      (node (ref "R_B_EN2") (pin "2") (pinfunction "2_2") (pintype "unspecified"))
    )
    (net (code "69") (name "extraPin1") (class "Default")
      (node (ref "ESP32") (pin "20") (pinfunction "IO12_20") (pintype "unspecified"))
      (node (ref "EXTRAPINS") (pin "1") (pinfunction "1_1") (pintype "unspecified"))
    )
    (net (code "70") (name "extraPin2") (class "Default")
      (node (ref "ESP32") (pin "21") (pinfunction "IO13_21") (pintype "unspecified"))
      (node (ref "EXTRAPINS") (pin "2") (pinfunction "2_2") (pintype "unspecified"))
    )
    (net (code "71") (name "extraPin3") (class "Default")
      (node (ref "ESP32") (pin "22") (pinfunction "IO14_22") (pintype "unspecified"))
      (node (ref "EXTRAPINS") (pin "3") (pinfunction "3_3") (pintype "unspecified"))
    )
    (net (code "72") (name "extraPin4") (class "Default")
      (node (ref "ESP32") (pin "23") (pinfunction "IO21_23") (pintype "unspecified"))
      (node (ref "EXTRAPINS") (pin "4") (pinfunction "4_4") (pintype "unspecified"))
    )
    (net (code "73") (name "unconnected-(BOOT_SW-Pad1)") (class "Default")
      (node (ref "BOOT_SW") (pin "1") (pinfunction "1_1") (pintype "unspecified+no_connect"))
    )
    (net (code "74") (name "unconnected-(BOOT_SW-Pad4)") (class "Default")
      (node (ref "BOOT_SW") (pin "4") (pinfunction "4_4") (pintype "unspecified+no_connect"))
    )
    (net (code "75") (name "unconnected-(ESP32-IO1-Pad39)") (class "Default")
      (node (ref "ESP32") (pin "39") (pinfunction "IO1_39") (pintype "unspecified+no_connect"))
    )
    (net (code "76") (name "unconnected-(ESP32-IO2-Pad38)") (class "Default")
      (node (ref "ESP32") (pin "38") (pinfunction "IO2_38") (pintype "unspecified+no_connect"))
    )
    (net (code "77") (name "unconnected-(ESP32-IO3-Pad15)") (class "Default")
      (node (ref "ESP32") (pin "15") (pinfunction "IO3_15") (pintype "unspecified+no_connect"))
    )
    (net (code "78") (name "unconnected-(ESP32-IO4-Pad4)") (class "Default")
      (node (ref "ESP32") (pin "4") (pinfunction "IO4_4") (pintype "unspecified+no_connect"))
    )
    (net (code "79") (name "unconnected-(ESP32-IO8-Pad12)") (class "Default")
      (node (ref "ESP32") (pin "12") (pinfunction "IO8_12") (pintype "unspecified+no_connect"))
    )
    (net (code "80") (name "unconnected-(ESP32-IO15-Pad8)") (class "Default")
      (node (ref "ESP32") (pin "8") (pinfunction "IO15_8") (pintype "unspecified+no_connect"))
    )
    (net (code "81") (name "unconnected-(ESP32-IO19-Pad13)") (class "Default")
      (node (ref "ESP32") (pin "13") (pinfunction "IO19_13") (pintype "unspecified+no_connect"))
    )
    (net (code "82") (name "unconnected-(ESP32-IO20-Pad14)") (class "Default")
      (node (ref "ESP32") (pin "14") (pinfunction "IO20_14") (pintype "unspecified+no_connect"))
    )
    (net (code "83") (name "unconnected-(ESP32-IO40-Pad33)") (class "Default")
      (node (ref "ESP32") (pin "33") (pinfunction "IO40_33") (pintype "unspecified+no_connect"))
    )
    (net (code "84") (name "unconnected-(ESP32-IO41-Pad34)") (class "Default")
      (node (ref "ESP32") (pin "34") (pinfunction "IO41_34") (pintype "unspecified+no_connect"))
    )
    (net (code "85") (name "unconnected-(ESP32-IO42-Pad35)") (class "Default")
      (node (ref "ESP32") (pin "35") (pinfunction "IO42_35") (pintype "unspecified+no_connect"))
    )
    (net (code "86") (name "unconnected-(ESP32-IO45-Pad26)") (class "Default")
      (node (ref "ESP32") (pin "26") (pinfunction "IO45_26") (pintype "unspecified+no_connect"))
    )
    (net (code "87") (name "unconnected-(ESP32-IO46-Pad16)") (class "Default")
      (node (ref "ESP32") (pin "16") (pinfunction "IO46_16") (pintype "unspecified+no_connect"))
    )
    (net (code "88") (name "unconnected-(ESP32-IO47-Pad24)") (class "Default")
      (node (ref "ESP32") (pin "24") (pinfunction "IO47_24") (pintype "unspecified+no_connect"))
    )
    (net (code "89") (name "unconnected-(ESP32-IO48-Pad25)") (class "Default")
      (node (ref "ESP32") (pin "25") (pinfunction "IO48_25") (pintype "unspecified+no_connect"))
    )
    (net (code "90") (name "unconnected-(IRLEDREF-A-Pad1)") (class "Default")
      (node (ref "IRLEDREF") (pin "1") (pinfunction "A_1") (pintype "input+no_connect"))
    )
    (net (code "91") (name "unconnected-(IRRECREF-OUT-Pad1)") (class "Default")
      (node (ref "IRRECREF") (pin "1") (pinfunction "OUT_1") (pintype "unspecified+no_connect"))
    )
    (net (code "92") (name "unconnected-(IRRECREF-VS-Pad3)") (class "Default")
      (node (ref "IRRECREF") (pin "3") (pinfunction "VS_3") (pintype "unspecified+no_connect"))
    )
    (net (code "93") (name "unconnected-(MUX_I2C-SC6-Pad22)") (class "Default")
      (node (ref "MUX_I2C") (pin "22") (pinfunction "SC6_22") (pintype "unspecified+no_connect"))
    )
    (net (code "94") (name "unconnected-(MUX_I2C-SC7-Pad24)") (class "Default")
      (node (ref "MUX_I2C") (pin "24") (pinfunction "SC7_24") (pintype "unspecified+no_connect"))
    )
    (net (code "95") (name "unconnected-(MUX_I2C-SD6-Pad21)") (class "Default")
      (node (ref "MUX_I2C") (pin "21") (pinfunction "SD6_21") (pintype "unspecified+no_connect"))
    )
    (net (code "96") (name "unconnected-(MUX_I2C-SD7-Pad23)") (class "Default")
      (node (ref "MUX_I2C") (pin "23") (pinfunction "SD7_23") (pintype "unspecified+no_connect"))
    )
    (net (code "97") (name "unconnected-(MUX_RX-B7-Pad13)") (class "Default")
      (node (ref "MUX_RX") (pin "13") (pinfunction "B7_13") (pintype "unspecified+no_connect"))
    )
    (net (code "98") (name "unconnected-(MUX_RX-B8-Pad12)") (class "Default")
      (node (ref "MUX_RX") (pin "12") (pinfunction "B8_12") (pintype "unspecified+no_connect"))
    )
    (net (code "99") (name "unconnected-(MUX_RX-NC-Pad6)") (class "Default")
      (node (ref "MUX_RX") (pin "6") (pinfunction "NC_6") (pintype "unspecified+no_connect"))
    )
    (net (code "100") (name "unconnected-(MUX_TX-B7-Pad13)") (class "Default")
      (node (ref "MUX_TX") (pin "13") (pinfunction "B7_13") (pintype "unspecified+no_connect"))
    )
    (net (code "101") (name "unconnected-(MUX_TX-B8-Pad12)") (class "Default")
      (node (ref "MUX_TX") (pin "12") (pinfunction "B8_12") (pintype "unspecified+no_connect"))
    )
    (net (code "102") (name "unconnected-(MUX_TX-NC-Pad6)") (class "Default")
      (node (ref "MUX_TX") (pin "6") (pinfunction "NC_6") (pintype "unspecified+no_connect"))
    )
    (net (code "103") (name "unconnected-(RGB-DOUT-Pad3)") (class "Default")
      (node (ref "RGB") (pin "3") (pinfunction "DOUT_3") (pintype "unspecified+no_connect"))
    )
    (net (code "104") (name "unconnected-(RST_SW-Pad2)") (class "Default")
      (node (ref "RST_SW") (pin "2") (pinfunction "2_2") (pintype "unspecified+no_connect"))
    )
    (net (code "105") (name "unconnected-(RST_SW-Pad3)") (class "Default")
      (node (ref "RST_SW") (pin "3") (pinfunction "3_3") (pintype "unspecified+no_connect"))
    )
    (net (code "106") (name "unconnected-(TOF_REF-GND-Pad2)") (class "Default")
      (node (ref "TOF_REF") (pin "2") (pinfunction "GND_2") (pintype "unspecified+no_connect"))
    )
    (net (code "107") (name "unconnected-(TOF_REF-GPIO1-Pad5)") (class "Default")
      (node (ref "TOF_REF") (pin "5") (pinfunction "GPIO1_5") (pintype "unspecified+no_connect"))
    )
    (net (code "108") (name "unconnected-(TOF_REF-SCL-Pad3)") (class "Default")
      (node (ref "TOF_REF") (pin "3") (pinfunction "SCL_3") (pintype "unspecified+no_connect"))
    )
    (net (code "109") (name "unconnected-(TOF_REF-SDA-Pad4)") (class "Default")
      (node (ref "TOF_REF") (pin "4") (pinfunction "SDA_4") (pintype "unspecified+no_connect"))
    )
    (net (code "110") (name "unconnected-(TOF_REF-VIN-Pad1)") (class "Default")
      (node (ref "TOF_REF") (pin "1") (pinfunction "VIN_1") (pintype "unspecified+no_connect"))
    )
    (net (code "111") (name "unconnected-(TOF_REF-XSHUT-Pad6)") (class "Default")
      (node (ref "TOF_REF") (pin "6") (pinfunction "XSHUT_6") (pintype "unspecified+no_connect"))
    )
    (net (code "112") (name "unconnected-(U7-1A-Pad12)") (class "Default")
      (node (ref "U7") (pin "12") (pinfunction "1A_12") (pintype "unspecified+no_connect"))
    )
    (net (code "113") (name "unconnected-(U7-1B-Pad11)") (class "Default")
      (node (ref "U7") (pin "11") (pinfunction "1B_11") (pintype "unspecified+no_connect"))
    )
    (net (code "114") (name "unconnected-(U7-2A-Pad13)") (class "Default")
      (node (ref "U7") (pin "13") (pinfunction "2A_13") (pintype "unspecified+no_connect"))
    )
    (net (code "115") (name "unconnected-(U7-2B-Pad14)") (class "Default")
      (node (ref "U7") (pin "14") (pinfunction "2B_14") (pintype "unspecified+no_connect"))
    )
    (net (code "116") (name "unconnected-(U7-DIR-Pad8)") (class "Default")
      (node (ref "U7") (pin "8") (pinfunction "DIR_8") (pintype "unspecified+no_connect"))
    )
    (net (code "117") (name "unconnected-(U7-EN#-Pad1)") (class "Default")
      (node (ref "U7") (pin "1") (pinfunction "EN#_1") (pintype "unspecified+no_connect"))
    )
    (net (code "118") (name "unconnected-(U7-GND-Pad9)") (class "Default")
      (node (ref "U7") (pin "9") (pinfunction "GND_9") (pintype "unspecified+no_connect"))
    )
    (net (code "119") (name "unconnected-(U7-GND-Pad15)") (class "Default")
      (node (ref "U7") (pin "15") (pinfunction "GND_15") (pintype "unspecified+no_connect"))
    )
    (net (code "120") (name "unconnected-(U7-MS1-Pad2)") (class "Default")
      (node (ref "U7") (pin "2") (pinfunction "MS1_2") (pintype "unspecified+no_connect"))
    )
    (net (code "121") (name "unconnected-(U7-MS2-Pad3)") (class "Default")
      (node (ref "U7") (pin "3") (pinfunction "MS2_3") (pintype "unspecified+no_connect"))
    )
    (net (code "122") (name "unconnected-(U7-MS3-Pad4)") (class "Default")
      (node (ref "U7") (pin "4") (pinfunction "MS3_4") (pintype "unspecified+no_connect"))
    )
    (net (code "123") (name "unconnected-(U7-RST#-Pad5)") (class "Default")
      (node (ref "U7") (pin "5") (pinfunction "RST#_5") (pintype "unspecified+no_connect"))
    )
    (net (code "124") (name "unconnected-(U7-SLP#-Pad6)") (class "Default")
      (node (ref "U7") (pin "6") (pinfunction "SLP#_6") (pintype "unspecified+no_connect"))
    )
    (net (code "125") (name "unconnected-(U7-STEP-Pad7)") (class "Default")
      (node (ref "U7") (pin "7") (pinfunction "STEP_7") (pintype "unspecified+no_connect"))
    )
    (net (code "126") (name "unconnected-(U7-VDD-Pad10)") (class "Default")
      (node (ref "U7") (pin "10") (pinfunction "VDD_10") (pintype "unspecified+no_connect"))
    )
    (net (code "127") (name "unconnected-(U7-VMOT-Pad16)") (class "Default")
      (node (ref "U7") (pin "16") (pinfunction "VMOT_16") (pintype "unspecified+no_connect"))
    )
    (net (code "128") (name "unconnected-(USB-EP-Pad6)") (class "Default")
      (node (ref "USB") (pin "6") (pinfunction "EP_6") (pintype "unspecified+no_connect"))
    )
    (net (code "129") (name "unconnected-(USB-EP-Pad7)") (class "Default")
      (node (ref "USB") (pin "7") (pinfunction "EP_7") (pintype "unspecified+no_connect"))
    )
    (net (code "130") (name "unconnected-(USB-EP-Pad8)") (class "Default")
      (node (ref "USB") (pin "8") (pinfunction "EP_8") (pintype "unspecified+no_connect"))
    )
    (net (code "131") (name "unconnected-(USB-EP-Pad9)") (class "Default")
      (node (ref "USB") (pin "9") (pinfunction "EP_9") (pintype "unspecified+no_connect"))
    )
    (net (code "132") (name "unconnected-(USB-ID-Pad4)") (class "Default")
      (node (ref "USB") (pin "4") (pinfunction "ID_4") (pintype "unspecified+no_connect"))
    )
    (net (code "133") (name "unconnected-(USB2UART-CHR0-Pad15)") (class "Default")
      (node (ref "USB2UART") (pin "15") (pinfunction "CHR0_15") (pintype "unspecified+no_connect"))
    )
    (net (code "134") (name "unconnected-(USB2UART-CHR1-Pad14)") (class "Default")
      (node (ref "USB2UART") (pin "14") (pinfunction "CHR1_14") (pintype "unspecified+no_connect"))
    )
    (net (code "135") (name "unconnected-(USB2UART-CHREN-Pad13)") (class "Default")
      (node (ref "USB2UART") (pin "13") (pinfunction "CHREN_13") (pintype "unspecified+no_connect"))
    )
    (net (code "136") (name "unconnected-(USB2UART-CTS-Pad23)") (class "Default")
      (node (ref "USB2UART") (pin "23") (pinfunction "CTS_23") (pintype "unspecified+no_connect"))
    )
    (net (code "137") (name "unconnected-(USB2UART-DCD-Pad1)") (class "Default")
      (node (ref "USB2UART") (pin "1") (pinfunction "DCD_1") (pintype "unspecified+no_connect"))
    )
    (net (code "138") (name "unconnected-(USB2UART-DSR-Pad27)") (class "Default")
      (node (ref "USB2UART") (pin "27") (pinfunction "DSR_27") (pintype "unspecified+no_connect"))
    )
    (net (code "139") (name "unconnected-(USB2UART-DTR-Pad28)") (class "Default")
      (node (ref "USB2UART") (pin "28") (pinfunction "DTR_28") (pintype "unspecified+no_connect"))
    )
    (net (code "140") (name "unconnected-(USB2UART-GPIO.0{slash}TXT-Pad19)") (class "Default")
      (node (ref "USB2UART") (pin "19") (pinfunction "GPIO.0/TXT_19") (pintype "unspecified+no_connect"))
    )
    (net (code "141") (name "unconnected-(USB2UART-GPIO.1{slash}RXT-Pad18)") (class "Default")
      (node (ref "USB2UART") (pin "18") (pinfunction "GPIO.1/RXT_18") (pintype "unspecified+no_connect"))
    )
    (net (code "142") (name "unconnected-(USB2UART-GPIO.2{slash}RS485-Pad17)") (class "Default")
      (node (ref "USB2UART") (pin "17") (pinfunction "GPIO.2/RS485_17") (pintype "unspecified+no_connect"))
    )
    (net (code "143") (name "unconnected-(USB2UART-GPIO.3{slash}WAKEUP-Pad16)") (class "Default")
      (node (ref "USB2UART") (pin "16") (pinfunction "GPIO.3/WAKEUP_16") (pintype "unspecified+no_connect"))
    )
    (net (code "144") (name "unconnected-(USB2UART-GPIO.4-Pad22)") (class "Default")
      (node (ref "USB2UART") (pin "22") (pinfunction "GPIO.4_22") (pintype "unspecified+no_connect"))
    )
    (net (code "145") (name "unconnected-(USB2UART-GPIO.5-Pad21)") (class "Default")
      (node (ref "USB2UART") (pin "21") (pinfunction "GPIO.5_21") (pintype "unspecified+no_connect"))
    )
    (net (code "146") (name "unconnected-(USB2UART-GPIO.6-Pad20)") (class "Default")
      (node (ref "USB2UART") (pin "20") (pinfunction "GPIO.6_20") (pintype "unspecified+no_connect"))
    )
    (net (code "147") (name "unconnected-(USB2UART-NC-Pad10)") (class "Default")
      (node (ref "USB2UART") (pin "10") (pinfunction "NC_10") (pintype "unspecified+no_connect"))
    )
    (net (code "148") (name "unconnected-(USB2UART-RI{slash}CLK-Pad2)") (class "Default")
      (node (ref "USB2UART") (pin "2") (pinfunction "RI/CLK_2") (pintype "unspecified+no_connect"))
    )
    (net (code "149") (name "unconnected-(USB2UART-RTS-Pad24)") (class "Default")
      (node (ref "USB2UART") (pin "24") (pinfunction "RTS_24") (pintype "unspecified+no_connect"))
    )
    (net (code "150") (name "unconnected-(USB2UART-SUSPEND-Pad12)") (class "Default")
      (node (ref "USB2UART") (pin "12") (pinfunction "SUSPEND_12") (pintype "unspecified+no_connect"))
    )
    (net (code "151") (name "unconnected-(USB2UART-SUSPENDb-Pad11)") (class "Default")
      (node (ref "USB2UART") (pin "11") (pinfunction "SUSPENDb_11") (pintype "unspecified+no_connect"))
    )
  )
)
